# Son1.net
KiCad netlist of a schematic drawn in EAGLE
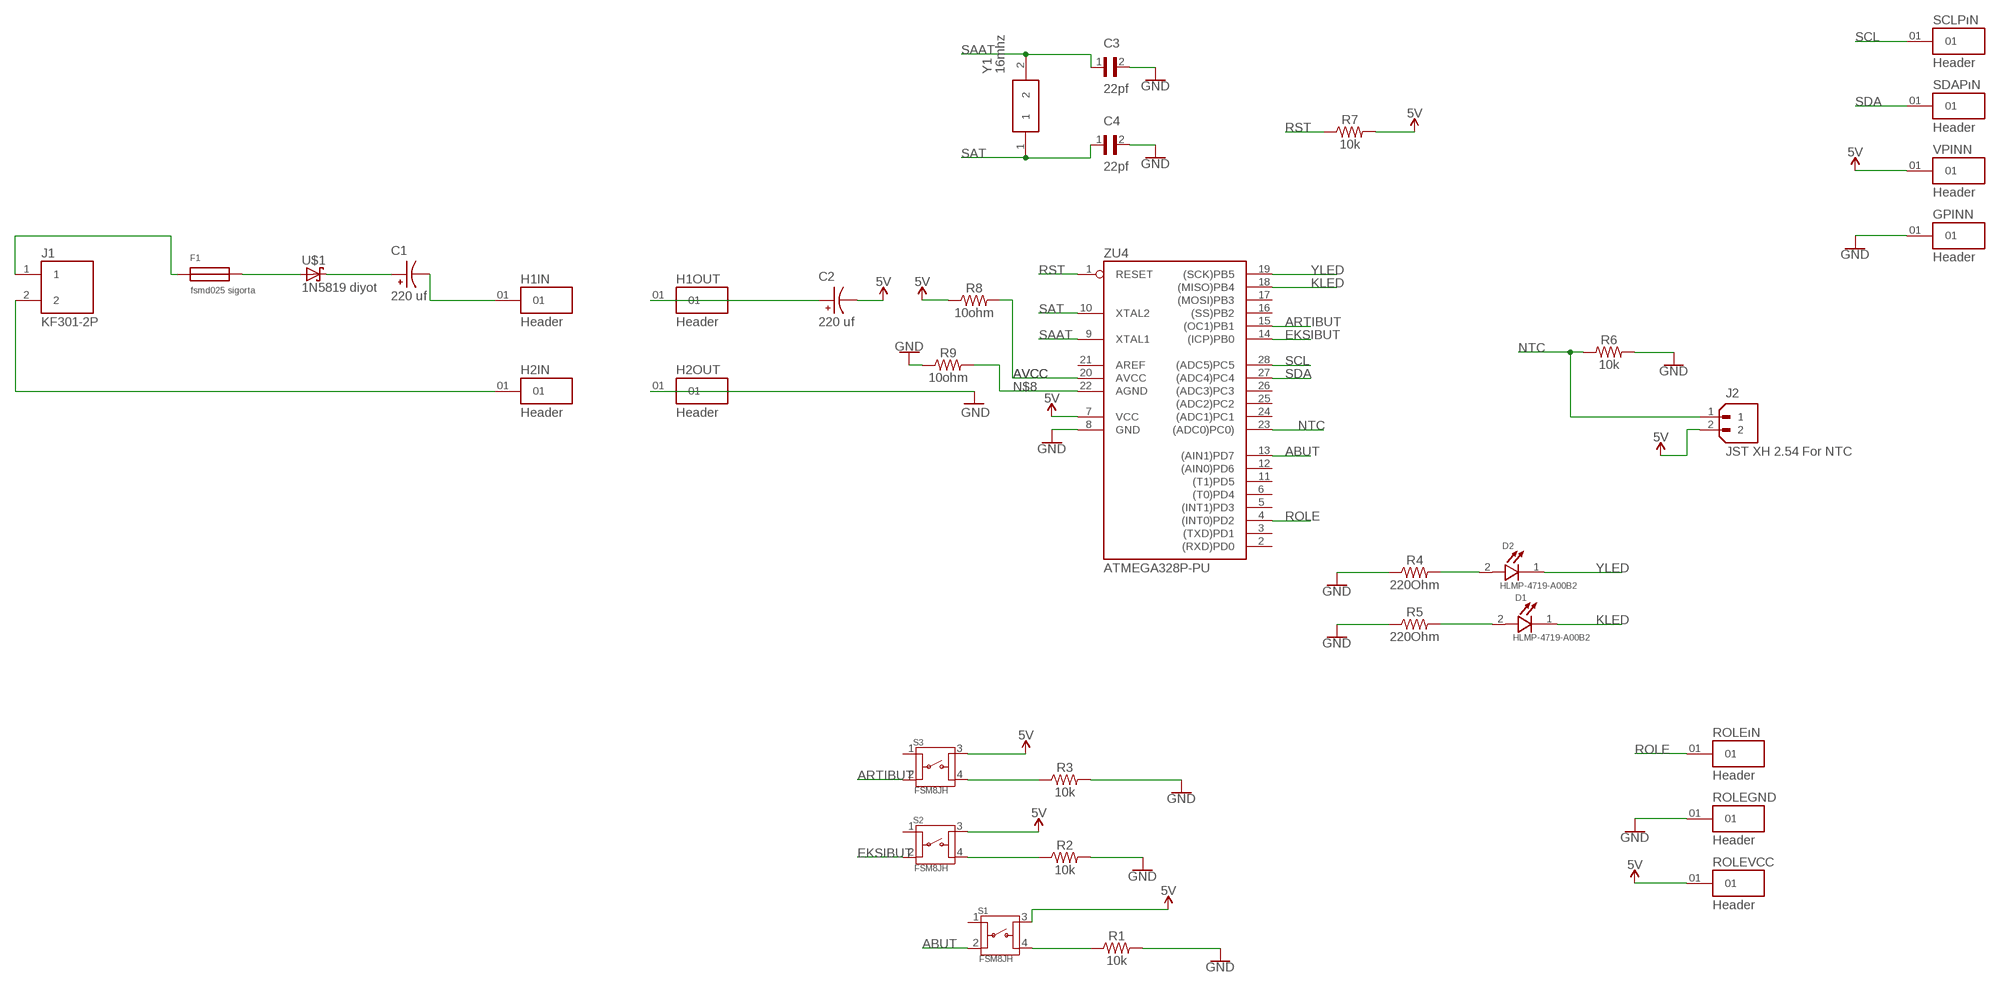
[diagram p0: schematic, sheet 1]

(export (version "E")
  (design (tool "Eeschema 10.0.6"))
  (components
    (comp (ref "C1")
      (value "220 uf")
      (footprint "eagle-import:CAP_EEEFP1E101AV")
      (fields (field (name "MF") "Panasonic") (field (name "MP") "EEEFP1E101AV"))
      (libsource (lib "eagle-import") (part "EEEFP1E101AV"))
    )
    (comp (ref "C2")
      (value "220 uf")
      (footprint "eagle-import:CAP_EEEFP1E101AV")
      (fields (field (name "MF") "Panasonic") (field (name "MP") "EEEFP1E101AV"))
      (libsource (lib "eagle-import") (part "EEEFP1E101AV"))
    )
    (comp (ref "C3")
      (value "22pf")
      (footprint "eagle-import:CAP_DE21XSA220KN3AX02F")
      (fields (field (name "MF") "Murata") (field (name "MP") "DE21XSA220KN3AX02F"))
      (libsource (lib "eagle-import") (part "DE21XSA220KN3AX02F"))
    )
    (comp (ref "C4")
      (value "22pf")
      (footprint "eagle-import:CAP_DE21XSA220KN3AX02F")
      (fields (field (name "MF") "Murata") (field (name "MP") "DE21XSA220KN3AX02F"))
      (libsource (lib "eagle-import") (part "DE21XSA220KN3AX02F"))
    )
    (comp (ref "D1")
      (value "HLMP-4719-A00B2")
      (footprint "eagle-import:LEDRD254W47D584H1078")
      (fields (field (name "MF") "Avago"))
      (libsource (lib "eagle-import") (part "HLMP-4719-A00B2"))
    )
    (comp (ref "D2")
      (value "HLMP-4719-A00B2")
      (footprint "eagle-import:LEDRD254W47D584H1078")
      (fields (field (name "MF") "Avago"))
      (libsource (lib "eagle-import") (part "HLMP-4719-A00B2"))
    )
    (comp (ref "F1")
      (value "fsmd025 sigorta")
      (footprint "eagle-import:0ZCN")
      (fields (field (name "MF") "Bel Fuse Inc.") (field (name "MP") "0ZCN0055FF2A"))
      (libsource (lib "eagle-import") (part "0ZCN0055FF2A"))
    )
    (comp (ref "GPINN")
      (value "Header")
      (footprint "eagle-import:SAMTEC_MTMM-101-X-X-S-X")
      (fields (field (name "MF") "Samtec") (field (name "MP") "MTMM-101-03-T-S-120"))
      (libsource (lib "eagle-import") (part "MTMM-101-X-X-S-X"))
    )
    (comp (ref "H1IN")
      (value "Header")
      (footprint "eagle-import:SAMTEC_MTMM-101-X-X-S-X")
      (fields (field (name "MF") "Samtec") (field (name "MP") "MTMM-101-03-T-S-120"))
      (libsource (lib "eagle-import") (part "MTMM-101-X-X-S-X"))
    )
    (comp (ref "H1OUT")
      (value "Header")
      (footprint "eagle-import:SAMTEC_MTMM-101-X-X-S-X")
      (fields (field (name "MF") "Samtec") (field (name "MP") "MTMM-101-03-T-S-120"))
      (libsource (lib "eagle-import") (part "MTMM-101-X-X-S-X"))
    )
    (comp (ref "H2IN")
      (value "Header")
      (footprint "eagle-import:SAMTEC_MTMM-101-X-X-S-X")
      (fields (field (name "MF") "Samtec") (field (name "MP") "MTMM-101-03-T-S-120"))
      (libsource (lib "eagle-import") (part "MTMM-101-X-X-S-X"))
    )
    (comp (ref "H2OUT")
      (value "Header")
      (footprint "eagle-import:SAMTEC_MTMM-101-X-X-S-X")
      (fields (field (name "MF") "Samtec") (field (name "MP") "MTMM-101-03-T-S-120"))
      (libsource (lib "eagle-import") (part "MTMM-101-X-X-S-X"))
    )
    (comp (ref "J1")
      (value "KF301-2P")
      (footprint "eagle-import:HANDSON_KF301-2P")
      (fields (field (name "MF") "Handson Technology"))
      (libsource (lib "eagle-import") (part "KF301-2P"))
    )
    (comp (ref "J2")
      (value "JST XH 2.54 For NTC")
      (footprint "eagle-import:JST_B2B-XH-A(LF)(SN)")
      (fields (field (name "MF") "JST Sales America Inc.") (field (name "MP") "B2B-XH-A(LF)(SN)"))
      (libsource (lib "eagle-import") (part "B2B-XH-A(LF)(SN)"))
    )
    (comp (ref "R1")
      (value "10k")
      (footprint "eagle-import:AXIAL-0.3")
      (libsource (lib "eagle-import") (part "10KOHM-HORIZ-1/4W-5%"))
    )
    (comp (ref "R2")
      (value "10k")
      (footprint "eagle-import:AXIAL-0.3")
      (libsource (lib "eagle-import") (part "10KOHM-HORIZ-1/4W-5%"))
    )
    (comp (ref "R3")
      (value "10k")
      (footprint "eagle-import:AXIAL-0.3")
      (libsource (lib "eagle-import") (part "10KOHM-HORIZ-1/4W-5%"))
    )
    (comp (ref "R4")
      (value "220Ohm")
      (footprint "eagle-import:AXIAL-0.3")
      (libsource (lib "eagle-import") (part "10MOHM-HORIZ-1/4W-5%"))
    )
    (comp (ref "R5")
      (value "220Ohm")
      (footprint "eagle-import:AXIAL-0.3")
      (libsource (lib "eagle-import") (part "10MOHM-HORIZ-1/4W-5%"))
    )
    (comp (ref "R6")
      (value "10k")
      (footprint "eagle-import:AXIAL-0.3")
      (libsource (lib "eagle-import") (part "10KOHM-HORIZ-1/4W-1%"))
    )
    (comp (ref "R7")
      (value "10k")
      (footprint "eagle-import:AXIAL-0.3")
      (libsource (lib "eagle-import") (part "10KOHM-HORIZ-1/4W-1%"))
    )
    (comp (ref "R8")
      (value "10ohm")
      (footprint "eagle-import:AXIAL-0.3")
      (libsource (lib "eagle-import") (part "10KOHM-HORIZ-1/4W-1%"))
    )
    (comp (ref "R9")
      (value "10ohm")
      (footprint "eagle-import:AXIAL-0.3")
      (libsource (lib "eagle-import") (part "10KOHM-HORIZ-1/4W-1%"))
    )
    (comp (ref "ROLEGND")
      (value "Header")
      (footprint "eagle-import:SAMTEC_MTMM-101-X-X-S-X")
      (fields (field (name "MF") "Samtec") (field (name "MP") "MTMM-101-03-T-S-120"))
      (libsource (lib "eagle-import") (part "MTMM-101-X-X-S-X"))
    )
    (comp (ref "ROLEıN")
      (value "Header")
      (footprint "eagle-import:SAMTEC_MTMM-101-X-X-S-X")
      (fields (field (name "MF") "Samtec") (field (name "MP") "MTMM-101-03-T-S-120"))
      (libsource (lib "eagle-import") (part "MTMM-101-X-X-S-X"))
    )
    (comp (ref "ROLEVCC")
      (value "Header")
      (footprint "eagle-import:SAMTEC_MTMM-101-X-X-S-X")
      (fields (field (name "MF") "Samtec") (field (name "MP") "MTMM-101-03-T-S-120"))
      (libsource (lib "eagle-import") (part "MTMM-101-X-X-S-X"))
    )
    (comp (ref "S1")
      (value "FSM8JH")
      (footprint "eagle-import:SW_FSM8JH")
      (fields (field (name "MF") "TE Connectivity"))
      (libsource (lib "eagle-import") (part "FSM8JH"))
    )
    (comp (ref "S2")
      (value "FSM8JH")
      (footprint "eagle-import:SW_FSM8JH")
      (fields (field (name "MF") "TE Connectivity"))
      (libsource (lib "eagle-import") (part "FSM8JH"))
    )
    (comp (ref "S3")
      (value "FSM8JH")
      (footprint "eagle-import:SW_FSM8JH")
      (fields (field (name "MF") "TE Connectivity"))
      (libsource (lib "eagle-import") (part "FSM8JH"))
    )
    (comp (ref "SCLPıN")
      (value "Header")
      (footprint "eagle-import:SAMTEC_MTMM-101-X-X-S-X")
      (fields (field (name "MF") "Samtec") (field (name "MP") "MTMM-101-03-T-S-120"))
      (libsource (lib "eagle-import") (part "MTMM-101-X-X-S-X"))
    )
    (comp (ref "SDAPıN")
      (value "Header")
      (footprint "eagle-import:SAMTEC_MTMM-101-X-X-S-X")
      (fields (field (name "MF") "Samtec") (field (name "MP") "MTMM-101-03-T-S-120"))
      (libsource (lib "eagle-import") (part "MTMM-101-X-X-S-X"))
    )
    (comp (ref "U$1")
      (value "1N5819 diyot")
      (footprint "eagle-import:SOD68")
      (fields (field (name "MF") "EIC Semiconductor") (field (name "MP") "BAT85"))
      (libsource (lib "eagle-import") (part "BAT85"))
    )
    (comp (ref "VPINN")
      (value "Header")
      (footprint "eagle-import:SAMTEC_MTMM-101-X-X-S-X")
      (fields (field (name "MF") "Samtec") (field (name "MP") "MTMM-101-03-T-S-120"))
      (libsource (lib "eagle-import") (part "MTMM-101-X-X-S-X"))
    )
    (comp (ref "Y1")
      (value "16mhz")
      (footprint "eagle-import:HC49SLF_1")
      (fields (field (name "MF") "Fox Electronics") (field (name "MP") "FOXSLF/160-20"))
      (libsource (lib "eagle-import") (part "FOXSLF_160-20"))
    )
    (comp (ref "ZU4")
      (value "ATMEGA328P-PU")
      (footprint "eagle-import:DIL28-3")
      (libsource (lib "eagle-import") (part "ATMEGA328P-PU"))
    )
  )
  (nets
    (net (code "1") (name "/ABUT") (class "Default")
      (node (ref "S1") (pin "2") (pinfunction "2_2") (pintype "passive"))
      (node (ref "ZU4") (pin "13") (pinfunction "(AIN1)PD7_13") (pintype "bidirectional"))
    )
    (net (code "2") (name "/ARTIBUT") (class "Default")
      (node (ref "S3") (pin "2") (pinfunction "2_2") (pintype "passive"))
      (node (ref "ZU4") (pin "15") (pinfunction "(OC1)PB1_15") (pintype "bidirectional"))
    )
    (net (code "3") (name "/AVCC") (class "Default")
      (node (ref "R8") (pin "P$2") (pinfunction "2_P$2") (pintype "passive"))
      (node (ref "ZU4") (pin "20") (pinfunction "AVCC_20") (pintype "power_in"))
    )
    (net (code "4") (name "/EKSIBUT") (class "Default")
      (node (ref "S2") (pin "2") (pinfunction "2_2") (pintype "passive"))
      (node (ref "ZU4") (pin "14") (pinfunction "(ICP)PB0_14") (pintype "bidirectional"))
    )
    (net (code "5") (name "/KLED") (class "Default")
      (node (ref "D1") (pin "1") (pinfunction "C_1") (pintype "passive"))
      (node (ref "ZU4") (pin "18") (pinfunction "(MISO)PB4_18") (pintype "bidirectional"))
    )
    (net (code "6") (name "/N$8") (class "Default")
      (node (ref "R9") (pin "P$2") (pinfunction "2_P$2") (pintype "passive"))
      (node (ref "ZU4") (pin "22") (pinfunction "AGND_22") (pintype "power_in"))
    )
    (net (code "7") (name "/NTC") (class "Default")
      (node (ref "J2") (pin "1") (pinfunction "1_1") (pintype "passive"))
      (node (ref "R6") (pin "P$1") (pinfunction "1_P$1") (pintype "passive"))
      (node (ref "ZU4") (pin "23") (pinfunction "(ADC0)PC0)_23") (pintype "bidirectional"))
    )
    (net (code "8") (name "/ROLE") (class "Default")
      (node (ref "ROLEıN") (pin "01") (pinfunction "01_01") (pintype "passive"))
      (node (ref "ZU4") (pin "4") (pinfunction "(INT0)PD2_4") (pintype "bidirectional"))
    )
    (net (code "9") (name "/RST") (class "Default")
      (node (ref "R7") (pin "P$1") (pinfunction "1_P$1") (pintype "passive"))
      (node (ref "ZU4") (pin "1") (pinfunction "RESET_1") (pintype "input"))
    )
    (net (code "10") (name "/SAAT") (class "Default")
      (node (ref "C3") (pin "1") (pinfunction "1_1") (pintype "passive"))
      (node (ref "Y1") (pin "2") (pinfunction "2_2") (pintype "bidirectional"))
      (node (ref "ZU4") (pin "9") (pinfunction "XTAL1_9") (pintype "bidirectional"))
    )
    (net (code "11") (name "/SAT") (class "Default")
      (node (ref "C4") (pin "1") (pinfunction "1_1") (pintype "passive"))
      (node (ref "Y1") (pin "1") (pinfunction "1_1") (pintype "bidirectional"))
      (node (ref "ZU4") (pin "10") (pinfunction "XTAL2_10") (pintype "bidirectional"))
    )
    (net (code "12") (name "/SCL") (class "Default")
      (node (ref "SCLPıN") (pin "01") (pinfunction "01_01") (pintype "passive"))
      (node (ref "ZU4") (pin "28") (pinfunction "(ADC5)PC5_28") (pintype "bidirectional"))
    )
    (net (code "13") (name "/SDA") (class "Default")
      (node (ref "SDAPıN") (pin "01") (pinfunction "01_01") (pintype "passive"))
      (node (ref "ZU4") (pin "27") (pinfunction "(ADC4)PC4_27") (pintype "bidirectional"))
    )
    (net (code "14") (name "/YLED") (class "Default")
      (node (ref "D2") (pin "1") (pinfunction "C_1") (pintype "passive"))
      (node (ref "ZU4") (pin "19") (pinfunction "(SCK)PB5_19") (pintype "bidirectional"))
    )
    (net (code "15") (name "5V") (class "Default")
      (node (ref "C2") (pin "2") (pinfunction "2_2") (pintype "passive"))
      (node (ref "J2") (pin "2") (pinfunction "2_2") (pintype "passive"))
      (node (ref "R7") (pin "P$2") (pinfunction "2_P$2") (pintype "passive"))
      (node (ref "R8") (pin "P$1") (pinfunction "1_P$1") (pintype "passive"))
      (node (ref "ROLEVCC") (pin "01") (pinfunction "01_01") (pintype "passive"))
      (node (ref "S1") (pin "3") (pinfunction "3_3") (pintype "passive"))
      (node (ref "S2") (pin "3") (pinfunction "3_3") (pintype "passive"))
      (node (ref "S3") (pin "3") (pinfunction "3_3") (pintype "passive"))
      (node (ref "VPINN") (pin "01") (pinfunction "01_01") (pintype "passive"))
      (node (ref "ZU4") (pin "7") (pinfunction "VCC_7") (pintype "power_in"))
    )
    (net (code "16") (name "GND") (class "Default")
      (node (ref "C3") (pin "2") (pinfunction "2_2") (pintype "passive"))
      (node (ref "C4") (pin "2") (pinfunction "2_2") (pintype "passive"))
      (node (ref "GPINN") (pin "01") (pinfunction "01_01") (pintype "passive"))
      (node (ref "H2OUT") (pin "01") (pinfunction "01_01") (pintype "passive"))
      (node (ref "R1") (pin "P$2") (pinfunction "2_P$2") (pintype "passive"))
      (node (ref "R2") (pin "P$2") (pinfunction "2_P$2") (pintype "passive"))
      (node (ref "R3") (pin "P$2") (pinfunction "2_P$2") (pintype "passive"))
      (node (ref "R4") (pin "P$1") (pinfunction "1_P$1") (pintype "passive"))
      (node (ref "R5") (pin "P$1") (pinfunction "1_P$1") (pintype "passive"))
      (node (ref "R6") (pin "P$2") (pinfunction "2_P$2") (pintype "passive"))
      (node (ref "R9") (pin "P$1") (pinfunction "1_P$1") (pintype "passive"))
      (node (ref "ROLEGND") (pin "01") (pinfunction "01_01") (pintype "passive"))
      (node (ref "ZU4") (pin "8") (pinfunction "GND_8") (pintype "power_in"))
    )
    (net (code "17") (name "Net-(C1-Pad2)") (class "Default")
      (node (ref "C1") (pin "2") (pinfunction "2_2") (pintype "passive"))
      (node (ref "H1IN") (pin "01") (pinfunction "01_01") (pintype "passive"))
    )
    (net (code "18") (name "Net-(C2-Pad1)") (class "Default")
      (node (ref "C2") (pin "1") (pinfunction "1_1") (pintype "passive"))
      (node (ref "H1OUT") (pin "01") (pinfunction "01_01") (pintype "passive"))
    )
    (net (code "19") (name "Net-(D1-A)") (class "Default")
      (node (ref "D1") (pin "2") (pinfunction "A_2") (pintype "passive"))
      (node (ref "R5") (pin "P$2") (pinfunction "2_P$2") (pintype "passive"))
    )
    (net (code "20") (name "Net-(D2-A)") (class "Default")
      (node (ref "D2") (pin "2") (pinfunction "A_2") (pintype "passive"))
      (node (ref "R4") (pin "P$2") (pinfunction "2_P$2") (pintype "passive"))
    )
    (net (code "21") (name "Net-(F1-PadP$1)") (class "Default")
      (node (ref "F1") (pin "P$1") (pinfunction "P$1_P$1") (pintype "bidirectional"))
      (node (ref "J1") (pin "1") (pinfunction "1_1") (pintype "passive"))
    )
    (net (code "22") (name "Net-(F1-PadP$2)") (class "Default")
      (node (ref "F1") (pin "P$2") (pinfunction "P$2_P$2") (pintype "bidirectional"))
      (node (ref "U$1") (pin "A") (pinfunction "A_A") (pintype "passive"))
    )
    (net (code "23") (name "Net-(H2IN-Pad01)") (class "Default")
      (node (ref "H2IN") (pin "01") (pinfunction "01_01") (pintype "passive"))
      (node (ref "J1") (pin "2") (pinfunction "2_2") (pintype "passive"))
    )
    (net (code "24") (name "Net-(R1-1)") (class "Default")
      (node (ref "R1") (pin "P$1") (pinfunction "1_P$1") (pintype "passive"))
      (node (ref "S1") (pin "4") (pinfunction "4_4") (pintype "passive"))
    )
    (net (code "25") (name "Net-(R2-1)") (class "Default")
      (node (ref "R2") (pin "P$1") (pinfunction "1_P$1") (pintype "passive"))
      (node (ref "S2") (pin "4") (pinfunction "4_4") (pintype "passive"))
    )
    (net (code "26") (name "Net-(R3-1)") (class "Default")
      (node (ref "R3") (pin "P$1") (pinfunction "1_P$1") (pintype "passive"))
      (node (ref "S3") (pin "4") (pinfunction "4_4") (pintype "passive"))
    )
    (net (code "27") (name "Net-(U$1-K)") (class "Default")
      (node (ref "C1") (pin "1") (pinfunction "1_1") (pintype "passive"))
      (node (ref "U$1") (pin "C") (pinfunction "K_C") (pintype "passive"))
    )
    (net (code "28") (name "unconnected-(S1-Pad1)") (class "Default")
      (node (ref "S1") (pin "1") (pinfunction "1_1") (pintype "passive"))
    )
    (net (code "29") (name "unconnected-(S2-Pad1)") (class "Default")
      (node (ref "S2") (pin "1") (pinfunction "1_1") (pintype "passive"))
    )
    (net (code "30") (name "unconnected-(S3-Pad1)") (class "Default")
      (node (ref "S3") (pin "1") (pinfunction "1_1") (pintype "passive"))
    )
    (net (code "31") (name "unconnected-(ZU4-(ADC1)PC1-Pad24)") (class "Default")
      (node (ref "ZU4") (pin "24") (pinfunction "(ADC1)PC1_24") (pintype "bidirectional"))
    )
    (net (code "32") (name "unconnected-(ZU4-(ADC2)PC2-Pad25)") (class "Default")
      (node (ref "ZU4") (pin "25") (pinfunction "(ADC2)PC2_25") (pintype "bidirectional"))
    )
    (net (code "33") (name "unconnected-(ZU4-(ADC3)PC3-Pad26)") (class "Default")
      (node (ref "ZU4") (pin "26") (pinfunction "(ADC3)PC3_26") (pintype "bidirectional"))
    )
    (net (code "34") (name "unconnected-(ZU4-(AIN0)PD6-Pad12)") (class "Default")
      (node (ref "ZU4") (pin "12") (pinfunction "(AIN0)PD6_12") (pintype "bidirectional"))
    )
    (net (code "35") (name "unconnected-(ZU4-(INT1)PD3-Pad5)") (class "Default")
      (node (ref "ZU4") (pin "5") (pinfunction "(INT1)PD3_5") (pintype "bidirectional"))
    )
    (net (code "36") (name "unconnected-(ZU4-(MOSI)PB3-Pad17)") (class "Default")
      (node (ref "ZU4") (pin "17") (pinfunction "(MOSI)PB3_17") (pintype "bidirectional"))
    )
    (net (code "37") (name "unconnected-(ZU4-(RXD)PD0-Pad2)") (class "Default")
      (node (ref "ZU4") (pin "2") (pinfunction "(RXD)PD0_2") (pintype "bidirectional"))
    )
    (net (code "38") (name "unconnected-(ZU4-(SS)PB2-Pad16)") (class "Default")
      (node (ref "ZU4") (pin "16") (pinfunction "(SS)PB2_16") (pintype "bidirectional"))
    )
    (net (code "39") (name "unconnected-(ZU4-(T0)PD4-Pad6)") (class "Default")
      (node (ref "ZU4") (pin "6") (pinfunction "(T0)PD4_6") (pintype "bidirectional"))
    )
    (net (code "40") (name "unconnected-(ZU4-(T1)PD5-Pad11)") (class "Default")
      (node (ref "ZU4") (pin "11") (pinfunction "(T1)PD5_11") (pintype "bidirectional"))
    )
    (net (code "41") (name "unconnected-(ZU4-(TXD)PD1-Pad3)") (class "Default")
      (node (ref "ZU4") (pin "3") (pinfunction "(TXD)PD1_3") (pintype "bidirectional"))
    )
    (net (code "42") (name "unconnected-(ZU4-AREF-Pad21)") (class "Default")
      (node (ref "ZU4") (pin "21") (pinfunction "AREF_21") (pintype "passive"))
    )
  )
)
